# mbed-enablement-platform_F_4.net
KiCad netlist of a schematic drawn in Altium Designer
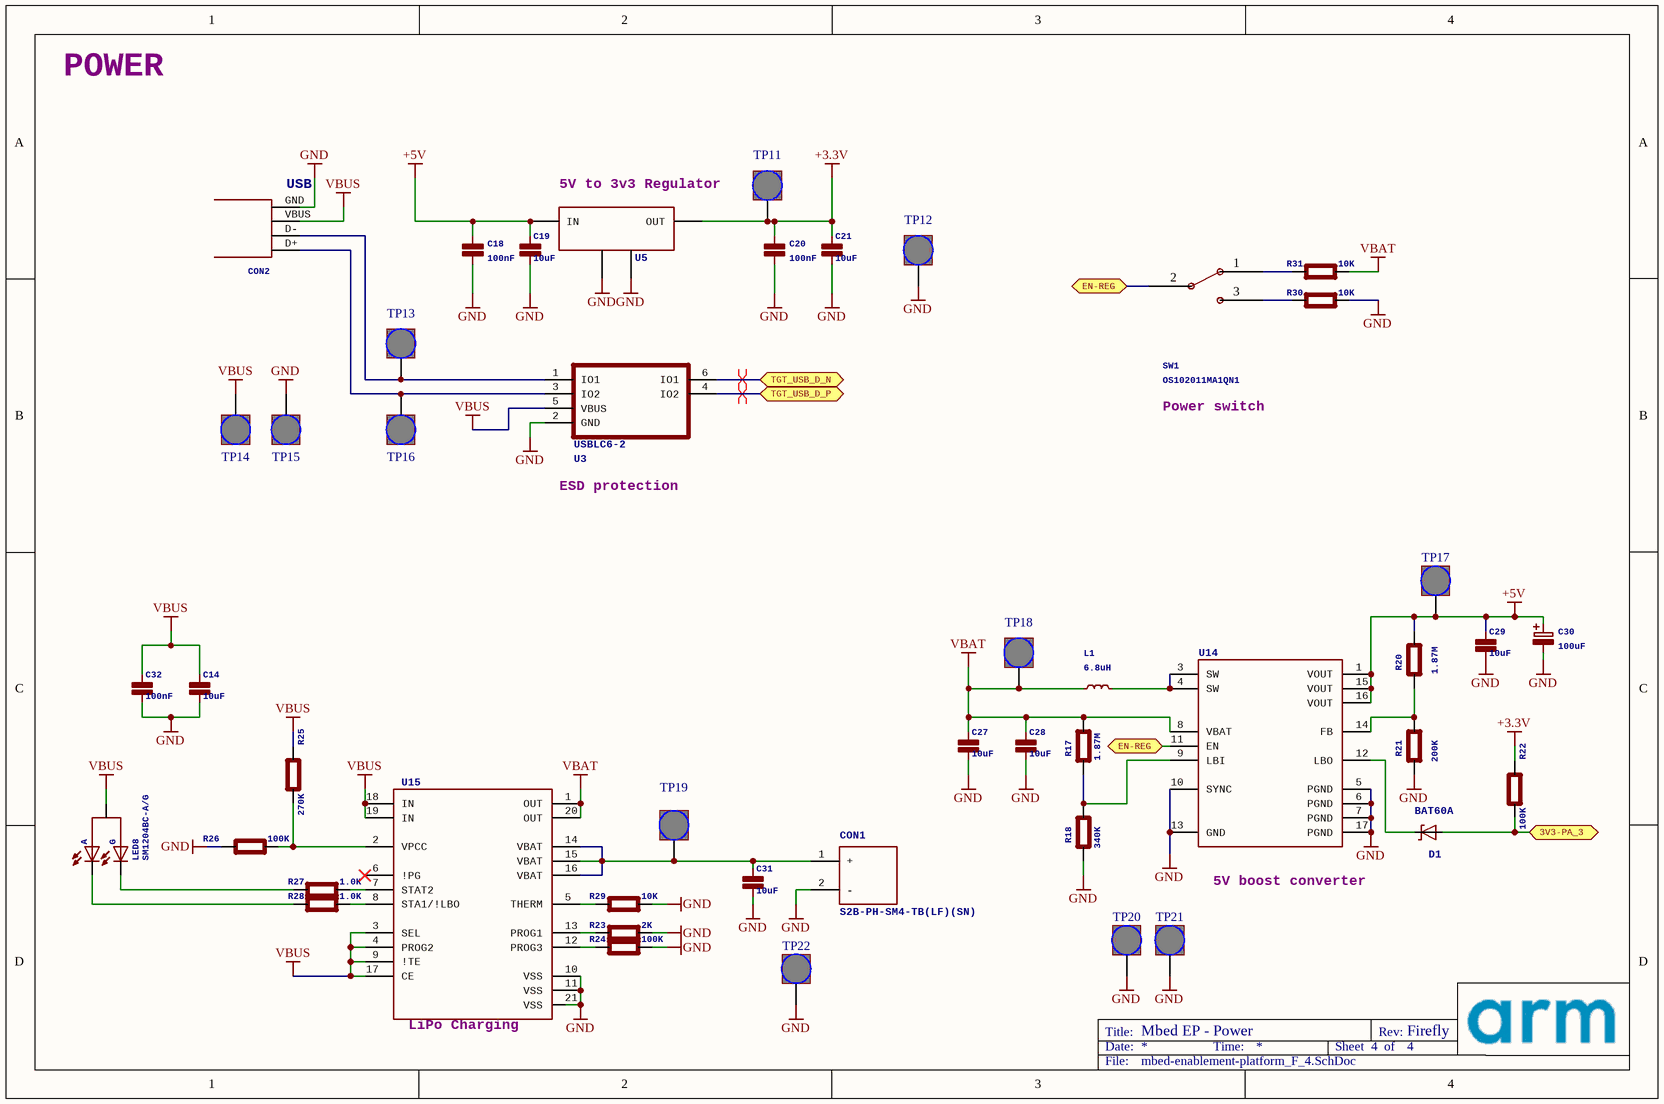
[diagram p0: mbed-enablement-platform_F_4.SchDoc]

(export (version "E")
  (design (tool "Eeschema 10.0.6"))
  (components
    (comp (ref "C14")
      (value "10uF")
      (footprint "0603")
      (description "Capacitor")
      (libsource (lib "mbed-workplace-env-mon") (part "CAPACITOR0603"))
    )
    (comp (ref "C18")
      (value "100nF")
      (footprint "0402")
      (description "Capacitor")
      (libsource (lib "mbed-workplace-env-mon") (part "CAPACITOR0402"))
    )
    (comp (ref "C19")
      (value "10uF")
      (footprint "0603")
      (description "Capacitor")
      (libsource (lib "mbed-workplace-env-mon") (part "CAPACITOR0603"))
    )
    (comp (ref "C20")
      (value "100nF")
      (footprint "0402")
      (description "Capacitor")
      (libsource (lib "mbed-workplace-env-mon") (part "CAPACITOR0402"))
    )
    (comp (ref "C21")
      (value "10uF")
      (footprint "0603")
      (description "Capacitor")
      (libsource (lib "mbed-workplace-env-mon") (part "CAPACITOR0603"))
    )
    (comp (ref "C27")
      (value "10uF")
      (footprint "0603")
      (description "Capacitor")
      (libsource (lib "mbed-workplace-env-mon") (part "CAPACITOR0603"))
    )
    (comp (ref "C28")
      (value "10uF")
      (footprint "0603")
      (description "Capacitor")
      (libsource (lib "mbed-workplace-env-mon") (part "CAPACITOR0603"))
    )
    (comp (ref "C29")
      (value "10uF")
      (footprint "0603")
      (description "Capacitor")
      (libsource (lib "mbed-workplace-env-mon") (part "CAPACITOR0603"))
    )
    (comp (ref "C30")
      (value "100uF")
      (footprint "SMC_B")
      (description "Polarised capacitor")
      (fields (field (name "MF") "Kemet"))
      (libsource (lib "mbed-workplace-env-mon") (part "CAPACITOR-POLARISEDB"))
    )
    (comp (ref "C31")
      (value "10uF")
      (footprint "0603")
      (description "Capacitor")
      (libsource (lib "mbed-workplace-env-mon") (part "CAPACITOR0603"))
    )
    (comp (ref "C32")
      (value "100nF")
      (footprint "0603")
      (description "Capacitor")
      (libsource (lib "mbed-workplace-env-mon") (part "CAPACITOR0603"))
    )
    (comp (ref "CON1")
      (value "S2B-PH-SM4-TB(LF)(SN)")
      (footprint "S2B-PH-SM4-TB(LF)(SN)")
      (description "2 Position 2 mm JST PH Series Pitch Surface Mount Side Entry Shrouded Header")
      (fields (field (name "MF") "JST"))
      (libsource (lib "mbed-workplace-env-mon") (part "S2B-PH-SM4-TB(LF)(SN)"))
    )
    (comp (ref "CON2")
      (value "47346-0001")
      (footprint "USB-MICRO-B-H")
      (description "USB Receptacle Horizontal Micro Type B")
      (fields (field (name "MF") "MOLEX") (field (name "USB") "USB"))
      (libsource (lib "mbed-workplace-env-mon") (part "47346-0001"))
    )
    (comp (ref "D1")
      (value "BAT60A")
      (footprint "SOD323")
      (description "SCHOTTKY DIODE")
      (fields (field (name "MF") "Infineon"))
      (libsource (lib "mbed-workplace-env-mon") (part "BAT60A"))
    )
    (comp (ref "L1")
      (value "6.8uH")
      (footprint "NR8040T6R8N")
      (description "Inductor")
      (fields (field (name "MF") "Taiyo Yuden"))
      (libsource (lib "mbed-workplace-env-mon") (part "INDUCTORNR8040T6R8N"))
    )
    (comp (ref "LED8")
      (value "SM1204BC-A/G")
      (footprint "CHIPLED_1204")
      (description "Dual Colour LED SMD Right Angle, Colour Amber/Green")
      (fields (field (name "MF") "Bivar") (field (name "G") "G") (field (name "A") "A"))
      (libsource (lib "mbed-workplace-env-mon") (part "SM1204BC-A/G"))
    )
    (comp (ref "R17")
      (value "1.87M")
      (footprint "0402")
      (description "Resistor")
      (libsource (lib "mbed-workplace-env-mon") (part "RESISTOR0402"))
    )
    (comp (ref "R18")
      (value "340K")
      (footprint "0402")
      (description "Resistor")
      (libsource (lib "mbed-workplace-env-mon") (part "RESISTOR0402"))
    )
    (comp (ref "R20")
      (value "1.87M")
      (footprint "0402")
      (description "Resistor")
      (libsource (lib "mbed-workplace-env-mon") (part "RESISTOR0402"))
    )
    (comp (ref "R21")
      (value "200K")
      (footprint "0402")
      (description "Resistor")
      (libsource (lib "mbed-workplace-env-mon") (part "RESISTOR0402"))
    )
    (comp (ref "R22")
      (value "100K")
      (footprint "0402")
      (description "Resistor")
      (libsource (lib "mbed-workplace-env-mon") (part "RESISTOR0402"))
    )
    (comp (ref "R23")
      (value "2K")
      (footprint "0402")
      (description "Resistor")
      (libsource (lib "mbed-workplace-env-mon") (part "RESISTOR0402"))
    )
    (comp (ref "R24")
      (value "100K")
      (footprint "0402")
      (description "Resistor")
      (libsource (lib "mbed-workplace-env-mon") (part "RESISTOR0402"))
    )
    (comp (ref "R25")
      (value "270K")
      (footprint "0402")
      (description "Resistor")
      (libsource (lib "mbed-workplace-env-mon") (part "RESISTOR0402"))
    )
    (comp (ref "R26")
      (value "100K")
      (footprint "0402")
      (description "Resistor")
      (libsource (lib "mbed-workplace-env-mon") (part "RESISTOR0402"))
    )
    (comp (ref "R27")
      (value "1.0K")
      (footprint "0402")
      (description "Resistor")
      (libsource (lib "mbed-workplace-env-mon") (part "RESISTOR0402"))
    )
    (comp (ref "R28")
      (value "1.0K")
      (footprint "0402")
      (description "Resistor")
      (libsource (lib "mbed-workplace-env-mon") (part "RESISTOR0402"))
    )
    (comp (ref "R29")
      (value "10K")
      (footprint "0402")
      (description "Resistor")
      (libsource (lib "mbed-workplace-env-mon") (part "RESISTOR0402"))
    )
    (comp (ref "R30")
      (value "10K")
      (footprint "0402")
      (description "Resistor")
      (libsource (lib "mbed-workplace-env-mon") (part "RESISTOR0402"))
    )
    (comp (ref "R31")
      (value "10K")
      (footprint "0402")
      (description "Resistor")
      (libsource (lib "mbed-workplace-env-mon") (part "RESISTOR0402"))
    )
    (comp (ref "SW1")
      (value "OS102011MA1QN1")
      (footprint "OS102011MA1QN1")
      (description "SWITCH SLIDE SPDT 100MA 12V")
      (fields (field (name "MF") "C&K Components"))
      (libsource (lib "mbed-workplace-env-mon") (part "OS102011MA1QN1"))
    )
    (comp (ref "TP11")
      (value "TP, 1.5mm")
      (footprint "TP1.5")
      (description "1.5mm round test point")
      (libsource (lib "mbed-workplace-env-mon") (part "TP1.5"))
    )
    (comp (ref "TP12")
      (value "TP, 1.5mm")
      (footprint "TP1.5")
      (description "1.5mm round test point")
      (libsource (lib "mbed-workplace-env-mon") (part "TP1.5"))
    )
    (comp (ref "TP13")
      (value "TP, 1.5mm")
      (footprint "TP1.5")
      (description "1.5mm round test point")
      (libsource (lib "mbed-workplace-env-mon") (part "TP1.5"))
    )
    (comp (ref "TP14")
      (value "TP, 1.5mm")
      (footprint "TP1.5")
      (description "1.5mm round test point")
      (libsource (lib "") (part "TP1.5_1"))
    )
    (comp (ref "TP15")
      (value "TP, 1.5mm")
      (footprint "TP1.5")
      (description "1.5mm round test point")
      (libsource (lib "") (part "TP1.5_1"))
    )
    (comp (ref "TP16")
      (value "TP, 1.5mm")
      (footprint "TP1.5")
      (description "1.5mm round test point")
      (libsource (lib "") (part "TP1.5_1"))
    )
    (comp (ref "TP17")
      (value "TP, 1.5mm")
      (footprint "TP1.5")
      (description "1.5mm round test point")
      (libsource (lib "mbed-workplace-env-mon") (part "TP1.5"))
    )
    (comp (ref "TP18")
      (value "TP, 1.5mm")
      (footprint "TP1.5")
      (description "1.5mm round test point")
      (libsource (lib "mbed-workplace-env-mon") (part "TP1.5"))
    )
    (comp (ref "TP19")
      (value "TP, 1.5mm")
      (footprint "TP1.5")
      (description "1.5mm round test point")
      (libsource (lib "mbed-workplace-env-mon") (part "TP1.5"))
    )
    (comp (ref "TP20")
      (value "TP, 1.5mm")
      (footprint "TP1.5")
      (description "1.5mm round test point")
      (libsource (lib "mbed-workplace-env-mon") (part "TP1.5"))
    )
    (comp (ref "TP21")
      (value "TP, 1.5mm")
      (footprint "TP1.5")
      (description "1.5mm round test point")
      (libsource (lib "mbed-workplace-env-mon") (part "TP1.5"))
    )
    (comp (ref "TP22")
      (value "TP, 1.5mm")
      (footprint "TP1.5")
      (description "1.5mm round test point")
      (libsource (lib "mbed-workplace-env-mon") (part "TP1.5"))
    )
    (comp (ref "U3")
      (value "USBLC6-2SC6SC6")
      (footprint "SOT23-6L")
      (description "ESD USB Protection Bi-Directional")
      (fields (field (name "MF") "STMicroelectronics") (field (name "USBLC6-2") "USBLC6-2"))
      (libsource (lib "mbed-workplace-env-mon") (part "USBLC6-2SC6SC6"))
    )
    (comp (ref "U5")
      (value "LDO Fixed Regulator 3.3v, 1.5A")
      (footprint "SOT223")
      (fields (field (name "MF") "Texas Instruments"))
      (libsource (lib "mbed-workplace-env-mon") (part "TL1963A-33DCYR"))
    )
    (comp (ref "U14")
      (value "Boost Converter 2A Switch, 96% Efficient Boost")
      (footprint "QFN-16")
      (fields (field (name "MF") "Texas Instruments"))
      (libsource (lib "mbed-workplace-env-mon") (part "TPS61090RSAR"))
    )
    (comp (ref "U15")
      (value "Lithium-Ion/Polymer Charger IC 4.2V (1000mA)")
      (footprint "QFN-20")
      (fields (field (name "MF") "Microchip"))
      (libsource (lib "mbed-workplace-env-mon") (part "MCP73871-2CCI/ML"))
    )
  )
  (nets
    (net (code "1") (name "+3.3V") (class "Default")
      (node (ref "C20") (pin "1") (pinfunction "P$1_1") (pintype "passive"))
      (node (ref "C21") (pin "1") (pinfunction "P$1_1") (pintype "passive"))
      (node (ref "R22") (pin "1") (pinfunction "P$1_1") (pintype "passive"))
      (node (ref "TP11") (pin "1") (pinfunction "1_1") (pintype "passive"))
      (node (ref "U5") (pin "3") (pinfunction "OUT_3") (pintype "passive"))
    )
    (net (code "2") (name "+5V") (class "Default")
      (node (ref "C18") (pin "1") (pinfunction "P$1_1") (pintype "passive"))
      (node (ref "C19") (pin "1") (pinfunction "P$1_1") (pintype "passive"))
      (node (ref "C29") (pin "1") (pinfunction "P$1_1") (pintype "passive"))
      (node (ref "C30") (pin "+") (pinfunction "+_+") (pintype "passive"))
      (node (ref "R20") (pin "1") (pinfunction "P$1_1") (pintype "passive"))
      (node (ref "TP17") (pin "1") (pinfunction "1_1") (pintype "passive"))
      (node (ref "U14") (pin "1") (pinfunction "VOUT_1") (pintype "passive"))
      (node (ref "U14") (pin "15") (pinfunction "VOUT_15") (pintype "passive"))
      (node (ref "U14") (pin "16") (pinfunction "VOUT_16") (pintype "passive"))
      (node (ref "U5") (pin "1") (pinfunction "IN_1") (pintype "passive"))
    )
    (net (code "3") (name "/3V3-PA_3") (class "Default")
      (node (ref "D1") (pin "A") (pinfunction "A_A") (pintype "passive"))
      (node (ref "R22") (pin "2") (pinfunction "P$2_2") (pintype "passive"))
    )
    (net (code "4") (name "/EN-REG") (class "Default")
      (node (ref "SW1") (pin "2") (pinfunction "2_2") (pintype "passive"))
      (node (ref "U14") (pin "11") (pinfunction "EN_11") (pintype "passive"))
    )
    (net (code "5") (name "/TGT_USB_D_N") (class "Default")
      (node (ref "U3") (pin "6") (pinfunction "IO1_6") (pintype "passive"))
    )
    (net (code "6") (name "/TGT_USB_D_P") (class "Default")
      (node (ref "U3") (pin "4") (pinfunction "IO2_4") (pintype "passive"))
    )
    (net (code "7") (name "GND") (class "Default")
      (node (ref "C14") (pin "2") (pinfunction "P$2_2") (pintype "passive"))
      (node (ref "C18") (pin "2") (pinfunction "P$2_2") (pintype "passive"))
      (node (ref "C19") (pin "2") (pinfunction "P$2_2") (pintype "passive"))
      (node (ref "C20") (pin "2") (pinfunction "P$2_2") (pintype "passive"))
      (node (ref "C21") (pin "2") (pinfunction "P$2_2") (pintype "passive"))
      (node (ref "C27") (pin "2") (pinfunction "P$2_2") (pintype "passive"))
      (node (ref "C28") (pin "2") (pinfunction "P$2_2") (pintype "passive"))
      (node (ref "C29") (pin "2") (pinfunction "P$2_2") (pintype "passive"))
      (node (ref "C30") (pin "-") (pinfunction "-_-") (pintype "passive"))
      (node (ref "C31") (pin "2") (pinfunction "P$2_2") (pintype "passive"))
      (node (ref "C32") (pin "2") (pinfunction "P$2_2") (pintype "passive"))
      (node (ref "CON1") (pin "2") (pinfunction "-_2") (pintype "passive"))
      (node (ref "CON2") (pin "GND") (pinfunction "GND_GND") (pintype "passive"))
      (node (ref "R18") (pin "2") (pinfunction "P$2_2") (pintype "passive"))
      (node (ref "R21") (pin "2") (pinfunction "P$2_2") (pintype "passive"))
      (node (ref "R23") (pin "2") (pinfunction "P$2_2") (pintype "passive"))
      (node (ref "R24") (pin "2") (pinfunction "P$2_2") (pintype "passive"))
      (node (ref "R26") (pin "1") (pinfunction "P$1_1") (pintype "passive"))
      (node (ref "R29") (pin "2") (pinfunction "P$2_2") (pintype "passive"))
      (node (ref "R30") (pin "2") (pinfunction "P$2_2") (pintype "passive"))
      (node (ref "TP12") (pin "1") (pinfunction "1_1") (pintype "passive"))
      (node (ref "TP15") (pin "1") (pinfunction "1_1") (pintype "passive"))
      (node (ref "TP20") (pin "1") (pinfunction "1_1") (pintype "passive"))
      (node (ref "TP21") (pin "1") (pinfunction "1_1") (pintype "passive"))
      (node (ref "TP22") (pin "1") (pinfunction "1_1") (pintype "passive"))
      (node (ref "U14") (pin "10") (pinfunction "SYNC_10") (pintype "passive"))
      (node (ref "U14") (pin "13") (pinfunction "GND_13") (pintype "passive"))
      (node (ref "U14") (pin "17") (pinfunction "PGND_17") (pintype "passive"))
      (node (ref "U14") (pin "5") (pinfunction "PGND_5") (pintype "passive"))
      (node (ref "U14") (pin "6") (pinfunction "PGND_6") (pintype "passive"))
      (node (ref "U14") (pin "7") (pinfunction "PGND_7") (pintype "passive"))
      (node (ref "U15") (pin "10") (pinfunction "VSS_10") (pintype "passive"))
      (node (ref "U15") (pin "11") (pinfunction "VSS_11") (pintype "passive"))
      (node (ref "U15") (pin "21") (pinfunction "VSS_21") (pintype "passive"))
      (node (ref "U3") (pin "2") (pinfunction "GND_2") (pintype "passive"))
      (node (ref "U5") (pin "2") (pinfunction "GND_2") (pintype "passive"))
      (node (ref "U5") (pin "4") (pinfunction "GND_4") (pintype "passive"))
    )
    (net (code "8") (name "Net-(C31-P$1)") (class "Default")
      (node (ref "C31") (pin "1") (pinfunction "P$1_1") (pintype "passive"))
      (node (ref "CON1") (pin "1") (pinfunction "+_1") (pintype "passive"))
      (node (ref "TP19") (pin "1") (pinfunction "1_1") (pintype "passive"))
      (node (ref "U15") (pin "14") (pinfunction "VBAT_14") (pintype "passive"))
      (node (ref "U15") (pin "15") (pinfunction "VBAT_15") (pintype "passive"))
      (node (ref "U15") (pin "16") (pinfunction "VBAT_16") (pintype "passive"))
    )
    (net (code "9") (name "Net-(CON2-PadD+)") (class "Default")
      (node (ref "CON2") (pin "D+") (pinfunction "D+_D+") (pintype "passive"))
      (node (ref "TP16") (pin "1") (pinfunction "1_1") (pintype "passive"))
      (node (ref "U3") (pin "3") (pinfunction "IO2_3") (pintype "passive"))
    )
    (net (code "10") (name "Net-(CON2-PadD-)") (class "Default")
      (node (ref "CON2") (pin "D-") (pinfunction "D-_D-") (pintype "passive"))
      (node (ref "TP13") (pin "1") (pinfunction "1_1") (pintype "passive"))
      (node (ref "U3") (pin "1") (pinfunction "IO1_1") (pintype "passive"))
    )
    (net (code "11") (name "Net-(L1-PadP$2)") (class "Default")
      (node (ref "L1") (pin "P$2") (pinfunction "P$2_P$2") (pintype "passive"))
      (node (ref "U14") (pin "3") (pinfunction "SW_3") (pintype "passive"))
      (node (ref "U14") (pin "4") (pinfunction "SW_4") (pintype "passive"))
    )
    (net (code "12") (name "Net-(LED8-2)") (class "Default")
      (node (ref "LED8") (pin "P$2") (pinfunction "2_P$2") (pintype "passive"))
      (node (ref "R28") (pin "1") (pinfunction "P$1_1") (pintype "passive"))
    )
    (net (code "13") (name "Net-(LED8-3)") (class "Default")
      (node (ref "LED8") (pin "P$3") (pinfunction "3_P$3") (pintype "passive"))
      (node (ref "R27") (pin "1") (pinfunction "P$1_1") (pintype "passive"))
    )
    (net (code "14") (name "Net-(R17-P$2)") (class "Default")
      (node (ref "R17") (pin "2") (pinfunction "P$2_2") (pintype "passive"))
      (node (ref "R18") (pin "1") (pinfunction "P$1_1") (pintype "passive"))
      (node (ref "U14") (pin "9") (pinfunction "LBI_9") (pintype "passive"))
    )
    (net (code "15") (name "Net-(R20-P$2)") (class "Default")
      (node (ref "R20") (pin "2") (pinfunction "P$2_2") (pintype "passive"))
      (node (ref "R21") (pin "1") (pinfunction "P$1_1") (pintype "passive"))
      (node (ref "U14") (pin "14") (pinfunction "FB_14") (pintype "passive"))
    )
    (net (code "16") (name "Net-(R23-P$1)") (class "Default")
      (node (ref "R23") (pin "1") (pinfunction "P$1_1") (pintype "passive"))
      (node (ref "U15") (pin "13") (pinfunction "PROG1_13") (pintype "passive"))
    )
    (net (code "17") (name "Net-(R24-P$1)") (class "Default")
      (node (ref "R24") (pin "1") (pinfunction "P$1_1") (pintype "passive"))
      (node (ref "U15") (pin "12") (pinfunction "PROG3_12") (pintype "passive"))
    )
    (net (code "18") (name "Net-(R25-P$2)") (class "Default")
      (node (ref "R25") (pin "2") (pinfunction "P$2_2") (pintype "passive"))
      (node (ref "R26") (pin "2") (pinfunction "P$2_2") (pintype "passive"))
      (node (ref "U15") (pin "2") (pinfunction "VPCC_2") (pintype "passive"))
    )
    (net (code "19") (name "Net-(R27-P$2)") (class "Default")
      (node (ref "R27") (pin "2") (pinfunction "P$2_2") (pintype "passive"))
      (node (ref "U15") (pin "7") (pinfunction "STAT2_7") (pintype "passive"))
    )
    (net (code "20") (name "Net-(R28-P$2)") (class "Default")
      (node (ref "R28") (pin "2") (pinfunction "P$2_2") (pintype "passive"))
      (node (ref "U15") (pin "8") (pinfunction "STA1/!LBO_8") (pintype "passive"))
    )
    (net (code "21") (name "Net-(R29-P$1)") (class "Default")
      (node (ref "R29") (pin "1") (pinfunction "P$1_1") (pintype "passive"))
      (node (ref "U15") (pin "5") (pinfunction "THERM_5") (pintype "passive"))
    )
    (net (code "22") (name "Net-(R30-P$1)") (class "Default")
      (node (ref "R30") (pin "1") (pinfunction "P$1_1") (pintype "passive"))
      (node (ref "SW1") (pin "3") (pinfunction "3_3") (pintype "passive"))
    )
    (net (code "23") (name "Net-(R31-P$1)") (class "Default")
      (node (ref "R31") (pin "1") (pinfunction "P$1_1") (pintype "passive"))
      (node (ref "SW1") (pin "1") (pinfunction "1_1") (pintype "passive"))
    )
    (net (code "24") (name "Net-(U14-LBO)") (class "Default")
      (node (ref "D1") (pin "K") (pinfunction "K_K") (pintype "passive"))
      (node (ref "U14") (pin "12") (pinfunction "LBO_12") (pintype "passive"))
    )
    (net (code "25") (name "VBAT") (class "Default")
      (node (ref "C27") (pin "1") (pinfunction "P$1_1") (pintype "passive"))
      (node (ref "C28") (pin "1") (pinfunction "P$1_1") (pintype "passive"))
      (node (ref "L1") (pin "P$1") (pinfunction "P$1_P$1") (pintype "passive"))
      (node (ref "R17") (pin "1") (pinfunction "P$1_1") (pintype "passive"))
      (node (ref "R31") (pin "2") (pinfunction "P$2_2") (pintype "passive"))
      (node (ref "TP18") (pin "1") (pinfunction "1_1") (pintype "passive"))
      (node (ref "U14") (pin "8") (pinfunction "VBAT_8") (pintype "passive"))
      (node (ref "U15") (pin "1") (pinfunction "OUT_1") (pintype "passive"))
      (node (ref "U15") (pin "20") (pinfunction "OUT_20") (pintype "passive"))
    )
    (net (code "26") (name "VBUS") (class "Default")
      (node (ref "C14") (pin "1") (pinfunction "P$1_1") (pintype "passive"))
      (node (ref "C32") (pin "1") (pinfunction "P$1_1") (pintype "passive"))
      (node (ref "CON2") (pin "VBUS") (pinfunction "VBUS_VBUS") (pintype "passive"))
      (node (ref "LED8") (pin "P$1") (pinfunction "1_P$1") (pintype "passive"))
      (node (ref "R25") (pin "1") (pinfunction "P$1_1") (pintype "passive"))
      (node (ref "TP14") (pin "1") (pinfunction "1_1") (pintype "passive"))
      (node (ref "U15") (pin "17") (pinfunction "CE_17") (pintype "passive"))
      (node (ref "U15") (pin "18") (pinfunction "IN_18") (pintype "passive"))
      (node (ref "U15") (pin "19") (pinfunction "IN_19") (pintype "passive"))
      (node (ref "U15") (pin "3") (pinfunction "SEL_3") (pintype "passive"))
      (node (ref "U15") (pin "4") (pinfunction "PROG2_4") (pintype "passive"))
      (node (ref "U15") (pin "9") (pinfunction "!TE_9") (pintype "passive"))
      (node (ref "U3") (pin "5") (pinfunction "VBUS_5") (pintype "passive"))
    )
    (net (code "27") (name "unconnected-(U15-!PG-Pad6)") (class "Default")
      (node (ref "U15") (pin "6") (pinfunction "!PG_6") (pintype "passive+no_connect"))
    )
  )
)
